# LvlTranslate.net
KiCad netlist of a schematic drawn in Altium Designer
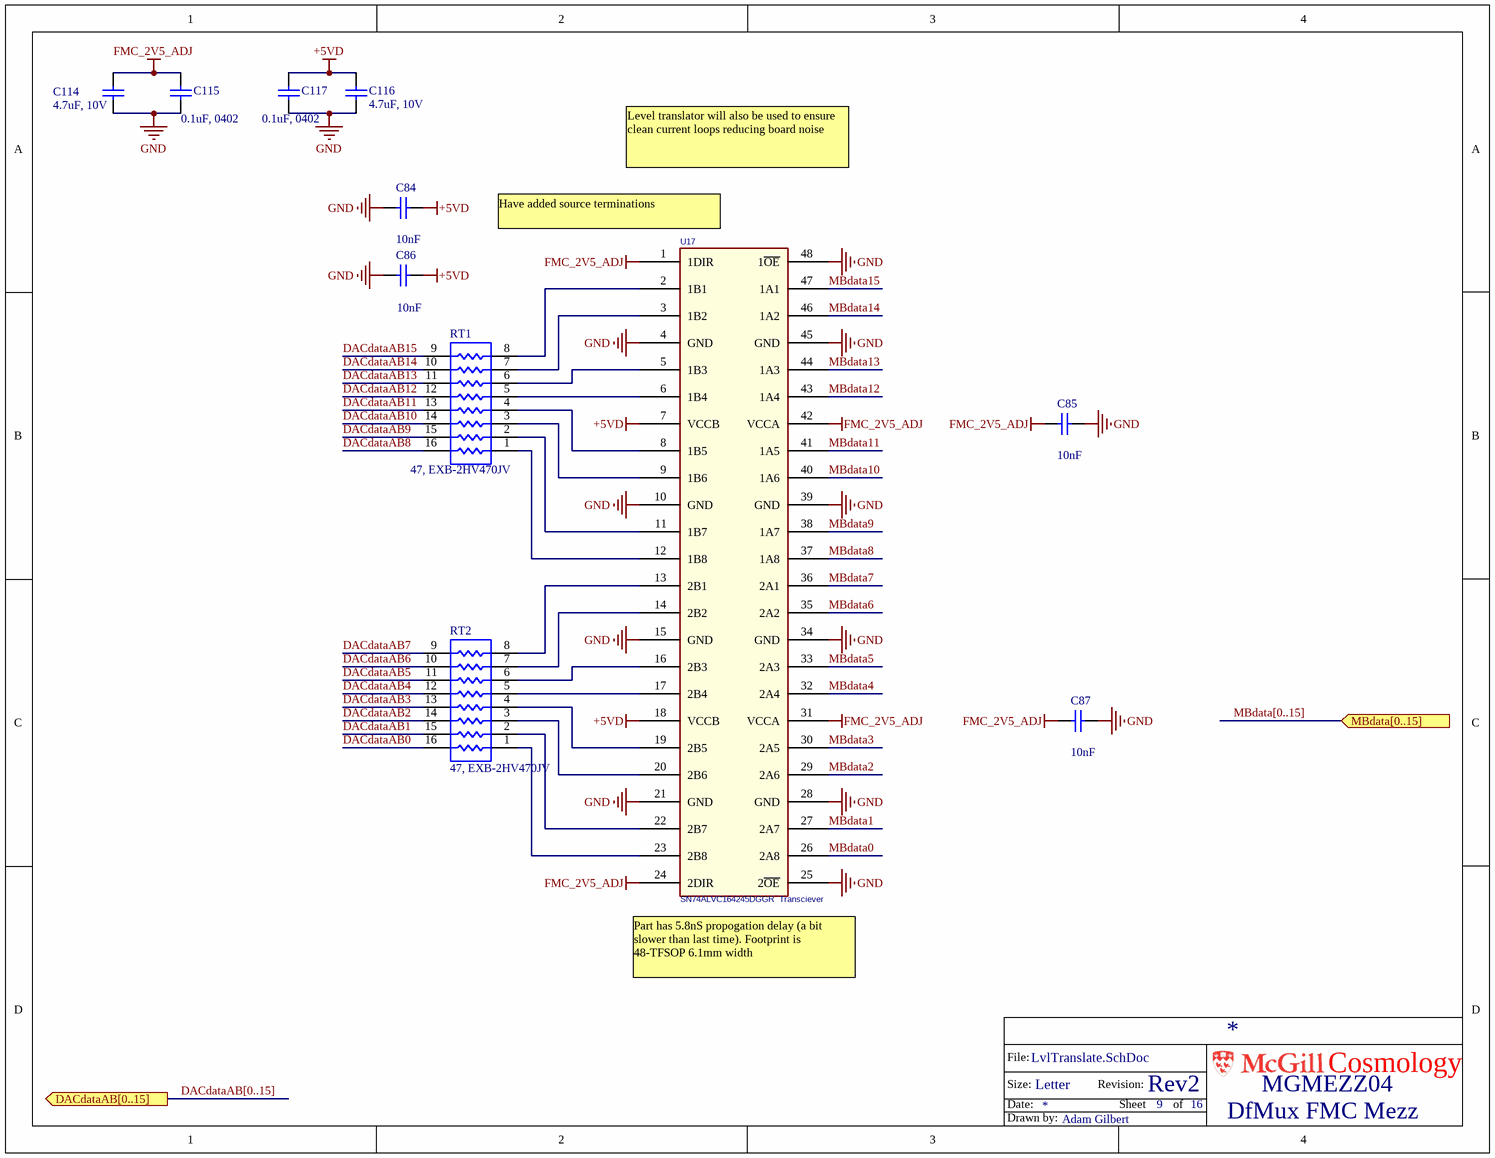
[diagram p0: LvlTranslate.SchDoc]

(export (version "E")
  (design (tool "Eeschema 10.0.6"))
  (components
    (comp (ref "C84")
      (value "10nF")
      (footprint "0402")
      (description "Capacitor, Ceramic, 0402")
      (fields (field (name "MANUFACTURER") "Murata Electronics North America"))
      (libsource (lib "MGMEZZ04") (part "CAP 0402"))
    )
    (comp (ref "C85")
      (value "10nF")
      (footprint "0402")
      (description "Capacitor, Ceramic, 0402")
      (fields (field (name "MANUFACTURER") "Murata Electronics North America"))
      (libsource (lib "MGMEZZ04") (part "CAP 0402"))
    )
    (comp (ref "C86")
      (value "10nF")
      (footprint "0402")
      (description "Capacitor, Ceramic, 0402")
      (fields (field (name "MANUFACTURER") "Murata Electronics North America"))
      (libsource (lib "MGMEZZ04") (part "CAP 0402"))
    )
    (comp (ref "C87")
      (value "10nF")
      (footprint "0402")
      (description "Capacitor, Ceramic, 0402")
      (fields (field (name "MANUFACTURER") "Murata Electronics North America"))
      (libsource (lib "MGMEZZ04") (part "CAP 0402"))
    )
    (comp (ref "C114")
      (value "4.7uF, 10V")
      (footprint "0805")
      (description "Capacitor, Ceramic, 0805")
      (fields (field (name "MANUFACTURER") "Taiyo Yuden"))
      (libsource (lib "MGMEZZ04") (part "CAP 0805"))
    )
    (comp (ref "C115")
      (value "0.1uF, 0402")
      (footprint "0402")
      (description "Capacitor, Ceramic, 0402")
      (fields (field (name "MANUFACTURER") "TDK Corporation"))
      (libsource (lib "MGMEZZ04") (part "CAP 0603"))
    )
    (comp (ref "C116")
      (value "4.7uF, 10V")
      (footprint "0805")
      (description "Capacitor, Ceramic, 0805")
      (fields (field (name "MANUFACTURER") "Taiyo Yuden"))
      (libsource (lib "MGMEZZ04") (part "CAP 0805"))
    )
    (comp (ref "C117")
      (value "0.1uF, 0402")
      (footprint "0402")
      (description "Capacitor, Ceramic, 0402")
      (fields (field (name "MANUFACTURER") "TDK Corporation"))
      (libsource (lib "MGMEZZ04") (part "CAP 0603"))
    )
    (comp (ref "RT1")
      (value "47, EXB-2HV470JV")
      (footprint "0402_Array_2HV")
      (description "RES ARRAY 47 OHM SMD")
      (fields (field (name "MANUFACTURER") "Panasonic - ECG"))
      (libsource (lib "MGMEZZ04") (part "Res_Pack"))
    )
    (comp (ref "RT2")
      (value "47, EXB-2HV470JV")
      (footprint "0402_Array_2HV")
      (description "RES ARRAY 47 OHM SMD")
      (fields (field (name "MANUFACTURER") "Panasonic - ECG"))
      (libsource (lib "MGMEZZ04") (part "Res_Pack"))
    )
    (comp (ref "U17")
      (value "SN74ALVC164245DGGR  Transciever")
      (footprint "TSSOP48-0.5mmpitch")
      (description "SN74ALVC164245DGGR Transciever")
      (fields (field (name "MANUFACTURER") "Texas Instruments"))
      (libsource (lib "MGMEZZ04") (part "SN74ALVC164245DGGR Transciever"))
    )
  )
  (nets
    (net (code "1") (name "+5VD") (class "Default")
      (node (ref "C116") (pin "2") (pinfunction "2_2") (pintype "passive"))
      (node (ref "C117") (pin "2") (pinfunction "2_2") (pintype "passive"))
      (node (ref "C84") (pin "2") (pinfunction "2_2") (pintype "passive"))
      (node (ref "C86") (pin "2") (pinfunction "2_2") (pintype "passive"))
      (node (ref "U17") (pin "18") (pinfunction "VCCB_18") (pintype "passive"))
      (node (ref "U17") (pin "7") (pinfunction "VCCB_7") (pintype "passive"))
    )
    (net (code "2") (name "/DACdataAB0") (class "Default")
      (node (ref "RT2") (pin "16") (pinfunction "16_16") (pintype "passive"))
    )
    (net (code "3") (name "/DACdataAB1") (class "Default")
      (node (ref "RT2") (pin "15") (pinfunction "15_15") (pintype "passive"))
    )
    (net (code "4") (name "/DACdataAB2") (class "Default")
      (node (ref "RT2") (pin "14") (pinfunction "14_14") (pintype "passive"))
    )
    (net (code "5") (name "/DACdataAB3") (class "Default")
      (node (ref "RT2") (pin "13") (pinfunction "13_13") (pintype "passive"))
    )
    (net (code "6") (name "/DACdataAB4") (class "Default")
      (node (ref "RT2") (pin "12") (pinfunction "12_12") (pintype "passive"))
    )
    (net (code "7") (name "/DACdataAB5") (class "Default")
      (node (ref "RT2") (pin "11") (pinfunction "11_11") (pintype "passive"))
    )
    (net (code "8") (name "/DACdataAB6") (class "Default")
      (node (ref "RT2") (pin "10") (pinfunction "10_10") (pintype "passive"))
    )
    (net (code "9") (name "/DACdataAB7") (class "Default")
      (node (ref "RT2") (pin "9") (pinfunction "9_9") (pintype "passive"))
    )
    (net (code "10") (name "/DACdataAB8") (class "Default")
      (node (ref "RT1") (pin "16") (pinfunction "16_16") (pintype "passive"))
    )
    (net (code "11") (name "/DACdataAB9") (class "Default")
      (node (ref "RT1") (pin "15") (pinfunction "15_15") (pintype "passive"))
    )
    (net (code "12") (name "/DACdataAB10") (class "Default")
      (node (ref "RT1") (pin "14") (pinfunction "14_14") (pintype "passive"))
    )
    (net (code "13") (name "/DACdataAB11") (class "Default")
      (node (ref "RT1") (pin "13") (pinfunction "13_13") (pintype "passive"))
    )
    (net (code "14") (name "/DACdataAB12") (class "Default")
      (node (ref "RT1") (pin "12") (pinfunction "12_12") (pintype "passive"))
    )
    (net (code "15") (name "/DACdataAB13") (class "Default")
      (node (ref "RT1") (pin "11") (pinfunction "11_11") (pintype "passive"))
    )
    (net (code "16") (name "/DACdataAB14") (class "Default")
      (node (ref "RT1") (pin "10") (pinfunction "10_10") (pintype "passive"))
    )
    (net (code "17") (name "/DACdataAB15") (class "Default")
      (node (ref "RT1") (pin "9") (pinfunction "9_9") (pintype "passive"))
    )
    (net (code "19") (name "/MBdata0") (class "Default")
      (node (ref "U17") (pin "26") (pinfunction "2A8_26") (pintype "passive"))
    )
    (net (code "20") (name "/MBdata1") (class "Default")
      (node (ref "U17") (pin "27") (pinfunction "2A7_27") (pintype "passive"))
    )
    (net (code "21") (name "/MBdata2") (class "Default")
      (node (ref "U17") (pin "29") (pinfunction "2A6_29") (pintype "passive"))
    )
    (net (code "22") (name "/MBdata3") (class "Default")
      (node (ref "U17") (pin "30") (pinfunction "2A5_30") (pintype "passive"))
    )
    (net (code "23") (name "/MBdata4") (class "Default")
      (node (ref "U17") (pin "32") (pinfunction "2A4_32") (pintype "passive"))
    )
    (net (code "24") (name "/MBdata5") (class "Default")
      (node (ref "U17") (pin "33") (pinfunction "2A3_33") (pintype "passive"))
    )
    (net (code "25") (name "/MBdata6") (class "Default")
      (node (ref "U17") (pin "35") (pinfunction "2A2_35") (pintype "passive"))
    )
    (net (code "26") (name "/MBdata7") (class "Default")
      (node (ref "U17") (pin "36") (pinfunction "2A1_36") (pintype "passive"))
    )
    (net (code "27") (name "/MBdata8") (class "Default")
      (node (ref "U17") (pin "37") (pinfunction "1A8_37") (pintype "passive"))
    )
    (net (code "28") (name "/MBdata9") (class "Default")
      (node (ref "U17") (pin "38") (pinfunction "1A7_38") (pintype "passive"))
    )
    (net (code "29") (name "/MBdata10") (class "Default")
      (node (ref "U17") (pin "40") (pinfunction "1A6_40") (pintype "passive"))
    )
    (net (code "30") (name "/MBdata11") (class "Default")
      (node (ref "U17") (pin "41") (pinfunction "1A5_41") (pintype "passive"))
    )
    (net (code "31") (name "/MBdata12") (class "Default")
      (node (ref "U17") (pin "43") (pinfunction "1A4_43") (pintype "passive"))
    )
    (net (code "32") (name "/MBdata13") (class "Default")
      (node (ref "U17") (pin "44") (pinfunction "1A3_44") (pintype "passive"))
    )
    (net (code "33") (name "/MBdata14") (class "Default")
      (node (ref "U17") (pin "46") (pinfunction "1A2_46") (pintype "passive"))
    )
    (net (code "34") (name "/MBdata15") (class "Default")
      (node (ref "U17") (pin "47") (pinfunction "1A1_47") (pintype "passive"))
    )
    (net (code "36") (name "FMC_2V5_ADJ") (class "Default")
      (node (ref "C114") (pin "2") (pinfunction "2_2") (pintype "passive"))
      (node (ref "C115") (pin "2") (pinfunction "2_2") (pintype "passive"))
      (node (ref "C85") (pin "1") (pinfunction "1_1") (pintype "passive"))
      (node (ref "C87") (pin "1") (pinfunction "1_1") (pintype "passive"))
      (node (ref "U17") (pin "1") (pinfunction "1DIR_1") (pintype "passive"))
      (node (ref "U17") (pin "24") (pinfunction "2DIR_24") (pintype "passive"))
      (node (ref "U17") (pin "31") (pinfunction "VCCA_31") (pintype "passive"))
      (node (ref "U17") (pin "42") (pinfunction "VCCA_42") (pintype "passive"))
    )
    (net (code "37") (name "GND") (class "Default")
      (node (ref "C114") (pin "1") (pinfunction "1_1") (pintype "passive"))
      (node (ref "C115") (pin "1") (pinfunction "1_1") (pintype "passive"))
      (node (ref "C116") (pin "1") (pinfunction "1_1") (pintype "passive"))
      (node (ref "C117") (pin "1") (pinfunction "1_1") (pintype "passive"))
      (node (ref "C84") (pin "1") (pinfunction "1_1") (pintype "passive"))
      (node (ref "C85") (pin "2") (pinfunction "2_2") (pintype "passive"))
      (node (ref "C86") (pin "1") (pinfunction "1_1") (pintype "passive"))
      (node (ref "C87") (pin "2") (pinfunction "2_2") (pintype "passive"))
      (node (ref "U17") (pin "10") (pinfunction "GND_10") (pintype "passive"))
      (node (ref "U17") (pin "15") (pinfunction "GND_15") (pintype "passive"))
      (node (ref "U17") (pin "21") (pinfunction "GND_21") (pintype "passive"))
      (node (ref "U17") (pin "25") (pinfunction "2~{OE}_25") (pintype "passive"))
      (node (ref "U17") (pin "28") (pinfunction "GND_28") (pintype "passive"))
      (node (ref "U17") (pin "34") (pinfunction "GND_34") (pintype "passive"))
      (node (ref "U17") (pin "39") (pinfunction "GND_39") (pintype "passive"))
      (node (ref "U17") (pin "4") (pinfunction "GND_4") (pintype "passive"))
      (node (ref "U17") (pin "45") (pinfunction "GND_45") (pintype "passive"))
      (node (ref "U17") (pin "48") (pinfunction "1~{OE}_48") (pintype "passive"))
    )
    (net (code "38") (name "Net-(U17-1B1)") (class "Default")
      (node (ref "RT1") (pin "8") (pinfunction "8_8") (pintype "passive"))
      (node (ref "U17") (pin "2") (pinfunction "1B1_2") (pintype "passive"))
    )
    (net (code "39") (name "Net-(U17-1B2)") (class "Default")
      (node (ref "RT1") (pin "7") (pinfunction "7_7") (pintype "passive"))
      (node (ref "U17") (pin "3") (pinfunction "1B2_3") (pintype "passive"))
    )
    (net (code "40") (name "Net-(U17-1B3)") (class "Default")
      (node (ref "RT1") (pin "6") (pinfunction "6_6") (pintype "passive"))
      (node (ref "U17") (pin "5") (pinfunction "1B3_5") (pintype "passive"))
    )
    (net (code "41") (name "Net-(U17-1B4)") (class "Default")
      (node (ref "RT1") (pin "5") (pinfunction "5_5") (pintype "passive"))
      (node (ref "U17") (pin "6") (pinfunction "1B4_6") (pintype "passive"))
    )
    (net (code "42") (name "Net-(U17-1B5)") (class "Default")
      (node (ref "RT1") (pin "4") (pinfunction "4_4") (pintype "passive"))
      (node (ref "U17") (pin "8") (pinfunction "1B5_8") (pintype "passive"))
    )
    (net (code "43") (name "Net-(U17-1B6)") (class "Default")
      (node (ref "RT1") (pin "3") (pinfunction "3_3") (pintype "passive"))
      (node (ref "U17") (pin "9") (pinfunction "1B6_9") (pintype "passive"))
    )
    (net (code "44") (name "Net-(U17-1B7)") (class "Default")
      (node (ref "RT1") (pin "2") (pinfunction "2_2") (pintype "passive"))
      (node (ref "U17") (pin "11") (pinfunction "1B7_11") (pintype "passive"))
    )
    (net (code "45") (name "Net-(U17-1B8)") (class "Default")
      (node (ref "RT1") (pin "1") (pinfunction "1_1") (pintype "passive"))
      (node (ref "U17") (pin "12") (pinfunction "1B8_12") (pintype "passive"))
    )
    (net (code "46") (name "Net-(U17-2B1)") (class "Default")
      (node (ref "RT2") (pin "8") (pinfunction "8_8") (pintype "passive"))
      (node (ref "U17") (pin "13") (pinfunction "2B1_13") (pintype "passive"))
    )
    (net (code "47") (name "Net-(U17-2B2)") (class "Default")
      (node (ref "RT2") (pin "7") (pinfunction "7_7") (pintype "passive"))
      (node (ref "U17") (pin "14") (pinfunction "2B2_14") (pintype "passive"))
    )
    (net (code "48") (name "Net-(U17-2B3)") (class "Default")
      (node (ref "RT2") (pin "6") (pinfunction "6_6") (pintype "passive"))
      (node (ref "U17") (pin "16") (pinfunction "2B3_16") (pintype "passive"))
    )
    (net (code "49") (name "Net-(U17-2B4)") (class "Default")
      (node (ref "RT2") (pin "5") (pinfunction "5_5") (pintype "passive"))
      (node (ref "U17") (pin "17") (pinfunction "2B4_17") (pintype "passive"))
    )
    (net (code "50") (name "Net-(U17-2B5)") (class "Default")
      (node (ref "RT2") (pin "4") (pinfunction "4_4") (pintype "passive"))
      (node (ref "U17") (pin "19") (pinfunction "2B5_19") (pintype "passive"))
    )
    (net (code "51") (name "Net-(U17-2B6)") (class "Default")
      (node (ref "RT2") (pin "3") (pinfunction "3_3") (pintype "passive"))
      (node (ref "U17") (pin "20") (pinfunction "2B6_20") (pintype "passive"))
    )
    (net (code "52") (name "Net-(U17-2B7)") (class "Default")
      (node (ref "RT2") (pin "2") (pinfunction "2_2") (pintype "passive"))
      (node (ref "U17") (pin "22") (pinfunction "2B7_22") (pintype "passive"))
    )
    (net (code "53") (name "Net-(U17-2B8)") (class "Default")
      (node (ref "RT2") (pin "1") (pinfunction "1_1") (pintype "passive"))
      (node (ref "U17") (pin "23") (pinfunction "2B8_23") (pintype "passive"))
    )
  )
)
